# SCH_PCB-1_2025-02-13.net
KiCad netlist of a schematic drawn in EasyEDA
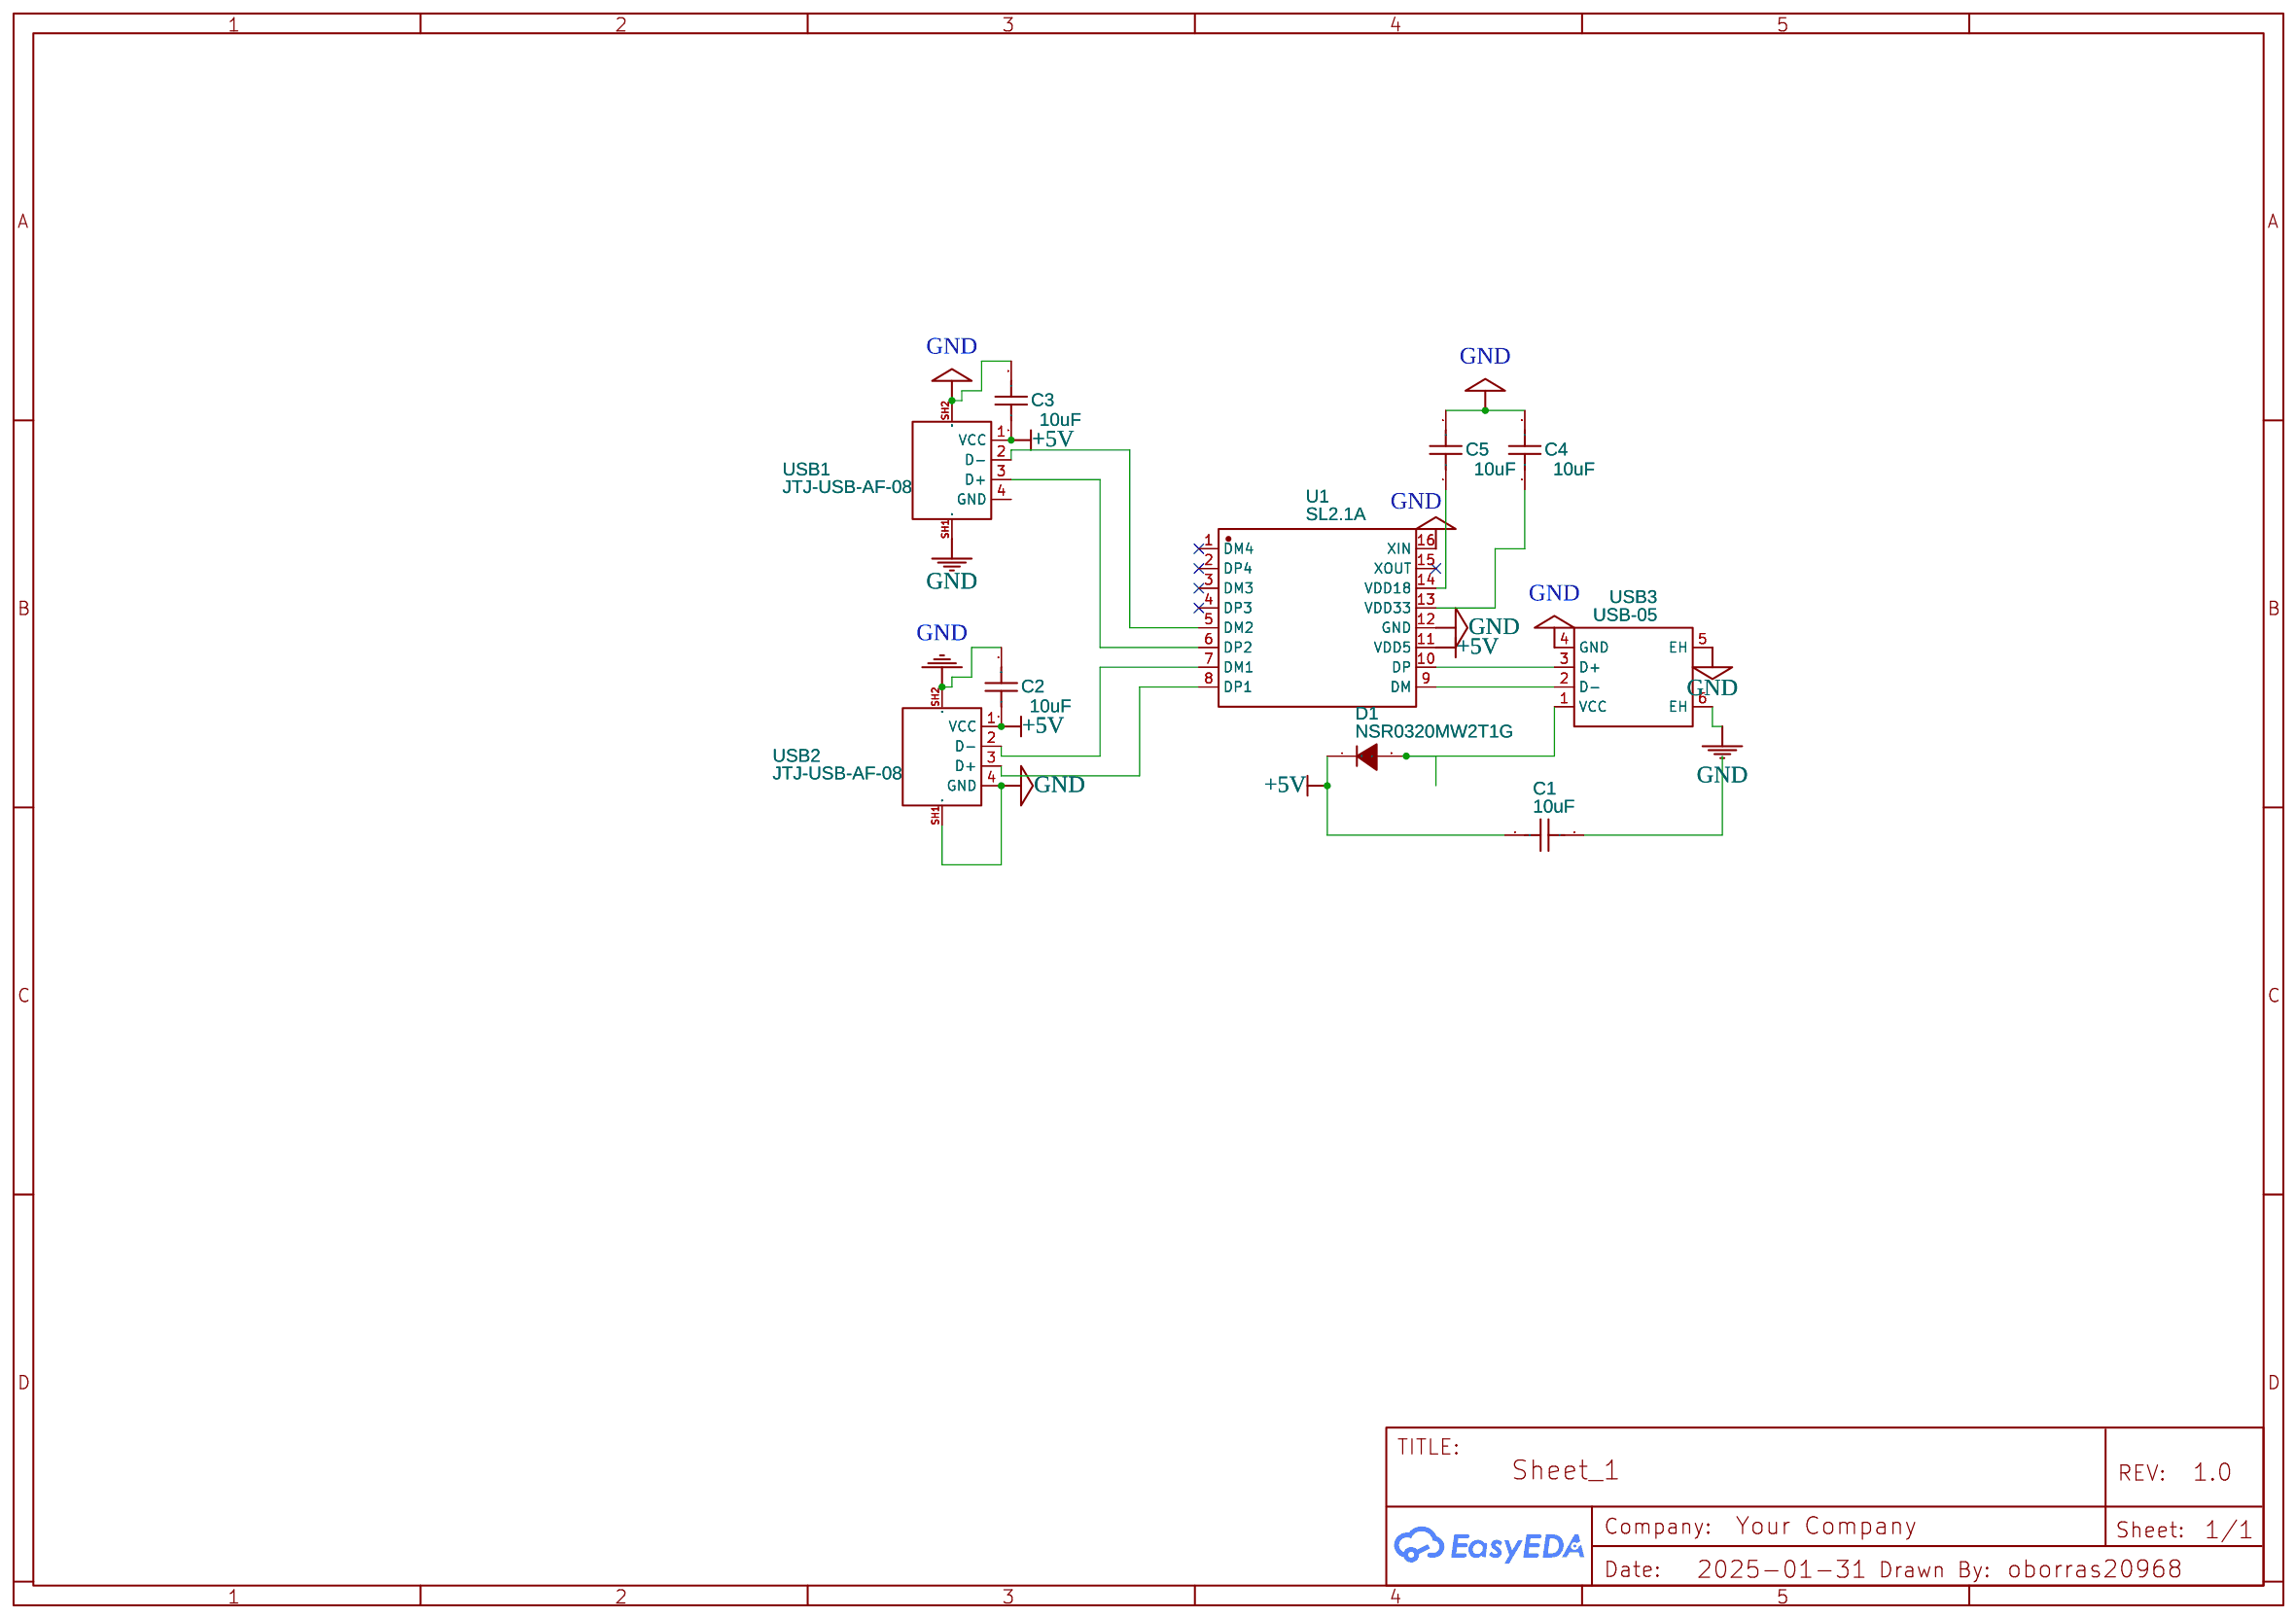
[diagram p0: schematic sheet]

(export (version "E")
  (design (tool "Eeschema 10.0.6"))
  (components
    (comp (ref "C1")
      (value "10uF")
      (fields
        (field (name "Manufacturer Part") "CL10A106KP8NNNC")
        (field (name "Manufacturer") "SAMSUNG(三星)")
      )
      (libsource (lib "") (part "CL10A106KP8NNNC_1"))
    )
    (comp (ref "C2")
      (value "10uF")
      (fields
        (field (name "Manufacturer Part") "CL10A106KP8NNNC")
        (field (name "Manufacturer") "SAMSUNG(三星)")
      )
      (libsource (lib "") (part "CL10A106KP8NNNC"))
    )
    (comp (ref "C3")
      (value "10uF")
      (fields
        (field (name "Manufacturer Part") "CL10A106KP8NNNC")
        (field (name "Manufacturer") "SAMSUNG(三星)")
      )
      (libsource (lib "") (part "CL10A106KP8NNNC"))
    )
    (comp (ref "C4")
      (value "10uF")
      (fields
        (field (name "Manufacturer Part") "CL10A106KP8NNNC")
        (field (name "Manufacturer") "SAMSUNG(三星)")
      )
      (libsource (lib "") (part "CL10A106KP8NNNC"))
    )
    (comp (ref "C5")
      (value "10uF")
      (fields
        (field (name "Manufacturer Part") "CL10A106KP8NNNC")
        (field (name "Manufacturer") "SAMSUNG(三星)")
      )
      (libsource (lib "") (part "CL10A106KP8NNNC"))
    )
    (comp (ref "D1")
      (value "NSR0320MW2T1G")
      (fields (field (name "Manufacturer") "onsemi(安森美)"))
      (libsource (lib "") (part "NSR0320MW2T1G"))
    )
    (comp (ref "U1")
      (value "SL2.1A")
      (fields (field (name "Manufacturer") "CoreChips(和芯润德)"))
      (libsource (lib "") (part "SL2.1A"))
    )
    (comp (ref "USB1")
      (value "JTJ-USB-AF-08")
      (fields (field (name "Manufacturer Part") "902-131A1011D10100") (field (name "Manufacturer") "精拓金"))
      (libsource (lib "") (part "JTJ-USB-AF-08"))
    )
    (comp (ref "USB2")
      (value "JTJ-USB-AF-08")
      (fields (field (name "Manufacturer Part") "902-131A1011D10100") (field (name "Manufacturer") "精拓金"))
      (libsource (lib "") (part "JTJ-USB-AF-08"))
    )
    (comp (ref "USB3")
      (value "USB-05")
      (fields (field (name "Manufacturer") "SOFNG(硕方)"))
      (libsource (lib "") (part "USB-05"))
    )
  )
  (nets
    (net (code "1") (name "+5V") (class "Default")
      (node (ref "C1") (pin "1") (pinfunction "1_1") (pintype "unspecified"))
      (node (ref "C2") (pin "1") (pinfunction "1_1") (pintype "unspecified"))
      (node (ref "C3") (pin "1") (pinfunction "1_1") (pintype "unspecified"))
      (node (ref "D1") (pin "1") (pinfunction "C_1") (pintype "unspecified"))
      (node (ref "U1") (pin "11") (pinfunction "VDD5_11") (pintype "unspecified"))
      (node (ref "USB1") (pin "1") (pinfunction "VCC_1") (pintype "input"))
      (node (ref "USB2") (pin "1") (pinfunction "VCC_1") (pintype "input"))
    )
    (net (code "2") (name "GND") (class "Default")
      (node (ref "C2") (pin "2") (pinfunction "2_2") (pintype "unspecified"))
      (node (ref "C3") (pin "2") (pinfunction "2_2") (pintype "unspecified"))
      (node (ref "C4") (pin "2") (pinfunction "2_2") (pintype "unspecified"))
      (node (ref "C5") (pin "2") (pinfunction "2_2") (pintype "unspecified"))
      (node (ref "U1") (pin "12") (pinfunction "GND_12") (pintype "unspecified"))
      (node (ref "U1") (pin "16") (pinfunction "XIN_16") (pintype "unspecified"))
      (node (ref "USB1") (pin "SH1") (pinfunction "SH1_SH1") (pintype "unspecified"))
      (node (ref "USB1") (pin "SH2") (pinfunction "SH2_SH2") (pintype "unspecified"))
      (node (ref "USB2") (pin "4") (pinfunction "GND_4") (pintype "input"))
      (node (ref "USB2") (pin "SH1") (pinfunction "SH1_SH1") (pintype "unspecified"))
      (node (ref "USB2") (pin "SH2") (pinfunction "SH2_SH2") (pintype "unspecified"))
      (node (ref "USB3") (pin "4") (pinfunction "GND_4") (pintype "input"))
      (node (ref "USB3") (pin "5") (pinfunction "EH_5") (pintype "unspecified"))
      (node (ref "USB3") (pin "6") (pinfunction "EH_6") (pintype "unspecified"))
    )
    (net (code "3") (name "Net-(D1-A)") (class "Default")
      (node (ref "D1") (pin "2") (pinfunction "A_2") (pintype "unspecified"))
      (node (ref "USB3") (pin "1") (pinfunction "VCC_1") (pintype "input"))
    )
    (net (code "4") (name "Net-(U1-DM)") (class "Default")
      (node (ref "U1") (pin "9") (pinfunction "DM_9") (pintype "unspecified"))
      (node (ref "USB3") (pin "2") (pinfunction "D-_2") (pintype "input"))
    )
    (net (code "5") (name "Net-(U1-DM1)") (class "Default")
      (node (ref "U1") (pin "7") (pinfunction "DM1_7") (pintype "unspecified"))
      (node (ref "USB2") (pin "2") (pinfunction "D-_2") (pintype "input"))
    )
    (net (code "6") (name "Net-(U1-DM2)") (class "Default")
      (node (ref "U1") (pin "5") (pinfunction "DM2_5") (pintype "unspecified"))
      (node (ref "USB1") (pin "2") (pinfunction "D-_2") (pintype "input"))
    )
    (net (code "7") (name "Net-(U1-DP)") (class "Default")
      (node (ref "U1") (pin "10") (pinfunction "DP_10") (pintype "unspecified"))
      (node (ref "USB3") (pin "3") (pinfunction "D+_3") (pintype "input"))
    )
    (net (code "8") (name "Net-(U1-DP1)") (class "Default")
      (node (ref "U1") (pin "8") (pinfunction "DP1_8") (pintype "unspecified"))
      (node (ref "USB2") (pin "3") (pinfunction "D+_3") (pintype "input"))
    )
    (net (code "9") (name "Net-(U1-DP2)") (class "Default")
      (node (ref "U1") (pin "6") (pinfunction "DP2_6") (pintype "unspecified"))
      (node (ref "USB1") (pin "3") (pinfunction "D+_3") (pintype "input"))
    )
    (net (code "10") (name "Net-(U1-VDD18)") (class "Default")
      (node (ref "C5") (pin "1") (pinfunction "1_1") (pintype "unspecified"))
      (node (ref "U1") (pin "14") (pinfunction "VDD18_14") (pintype "unspecified"))
    )
    (net (code "11") (name "Net-(U1-VDD33)") (class "Default")
      (node (ref "C4") (pin "1") (pinfunction "1_1") (pintype "unspecified"))
      (node (ref "U1") (pin "13") (pinfunction "VDD33_13") (pintype "unspecified"))
    )
    (net (code "12") (name "unconnected-(C1-Pad2)") (class "Default")
      (node (ref "C1") (pin "2") (pinfunction "2_2") (pintype "unspecified"))
    )
    (net (code "13") (name "unconnected-(U1-DM3-Pad3)") (class "Default")
      (node (ref "U1") (pin "3") (pinfunction "DM3_3") (pintype "unspecified+no_connect"))
    )
    (net (code "14") (name "unconnected-(U1-DM4-Pad1)") (class "Default")
      (node (ref "U1") (pin "1") (pinfunction "DM4_1") (pintype "unspecified+no_connect"))
    )
    (net (code "15") (name "unconnected-(U1-DP3-Pad4)") (class "Default")
      (node (ref "U1") (pin "4") (pinfunction "DP3_4") (pintype "unspecified+no_connect"))
    )
    (net (code "16") (name "unconnected-(U1-DP4-Pad2)") (class "Default")
      (node (ref "U1") (pin "2") (pinfunction "DP4_2") (pintype "unspecified+no_connect"))
    )
    (net (code "17") (name "unconnected-(U1-XOUT-Pad15)") (class "Default")
      (node (ref "U1") (pin "15") (pinfunction "XOUT_15") (pintype "unspecified+no_connect"))
    )
    (net (code "18") (name "unconnected-(USB1-GND-Pad4)") (class "Default")
      (node (ref "USB1") (pin "4") (pinfunction "GND_4") (pintype "input"))
    )
  )
)
